# LED_RING_12V_00.net
KiCad netlist of a schematic drawn in Altium Designer
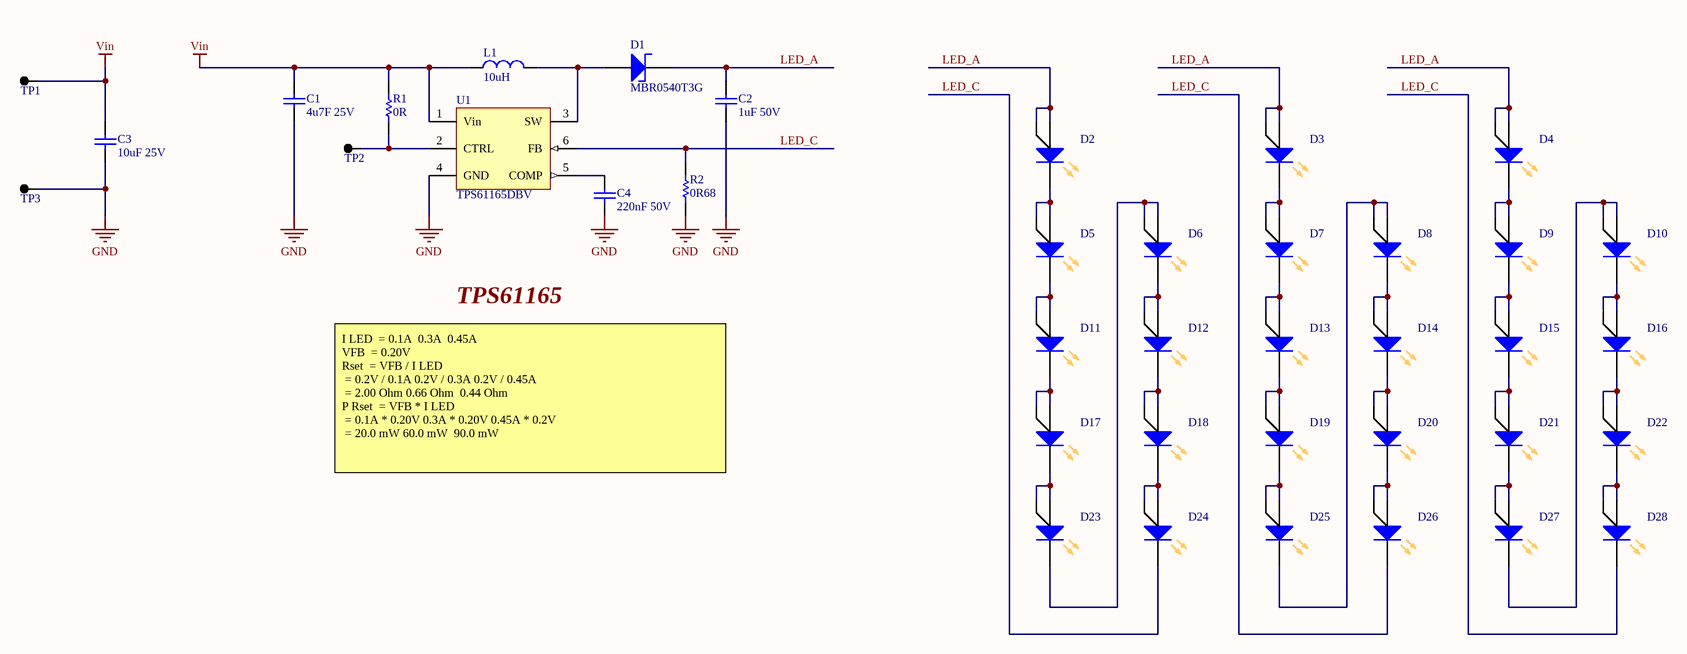
[diagram p0: LED_RING_12V_00.SchDoc]

(export (version "E")
  (design (tool "Eeschema 10.0.6"))
  (components
    (comp (ref "C1")
      (value "4u7F 25V")
      (footprint "C0805_N")
      (description "Capacitor Ceramic")
      (fields (field (name "Comment") "CAP_CERAMIC"))
      (libsource (lib "Phyx_Components") (part "CAP_CERAMIC"))
    )
    (comp (ref "C2")
      (value "1uF 50V")
      (footprint "C0805_N")
      (description "Capacitor Ceramic")
      (fields (field (name "Comment") "CAP_CERAMIC"))
      (libsource (lib "Phyx_Components") (part "CAP_CERAMIC"))
    )
    (comp (ref "C3")
      (value "10uF 25V")
      (footprint "C1206_N")
      (description "Capacitor Ceramic")
      (fields (field (name "Comment") "CAP_CERAMIC"))
      (libsource (lib "Phyx_Components") (part "CAP_CERAMIC"))
    )
    (comp (ref "C4")
      (value "220nF 50V")
      (footprint "C0603_N")
      (description "Capacitor Ceramic")
      (fields (field (name "Comment") "CAP_CERAMIC"))
      (libsource (lib "Phyx_Components") (part "CAP_CERAMIC"))
    )
    (comp (ref "D1")
      (value "MBR0540T3G")
      (footprint "ON_SOD-123FL")
      (description "=Description")
      (fields (field (name "Comment") "MBR0540T3G Schottky ULTRAFAST, 500MA, 40V"))
      (libsource (lib "Phyx_Components") (part "Schottky_21"))
    )
    (comp (ref "D2")
      (value "5630 5630AZLxx Lite ON LED")
      (footprint "LED_LM561A")
      (description "LED # LiteOn LTW-5630AZL27")
      (libsource (lib "Phyx_Components") (part "LED_5630AZLxx"))
    )
    (comp (ref "D3")
      (value "5630 5630AZLxx Lite ON LED")
      (footprint "LED_LM561A")
      (description "LED # LiteOn LTW-5630AZL27")
      (libsource (lib "Phyx_Components") (part "LED_5630AZLxx"))
    )
    (comp (ref "D4")
      (value "5630 5630AZLxx Lite ON LED")
      (footprint "LED_LM561A")
      (description "LED # LiteOn LTW-5630AZL27")
      (libsource (lib "Phyx_Components") (part "LED_5630AZLxx"))
    )
    (comp (ref "D5")
      (value "5630 5630AZLxx Lite ON LED")
      (footprint "LED_LM561A")
      (description "LED # LiteOn LTW-5630AZL27")
      (libsource (lib "Phyx_Components") (part "LED_5630AZLxx"))
    )
    (comp (ref "D6")
      (value "5630 5630AZLxx Lite ON LED")
      (footprint "LED_LM561A")
      (description "LED # LiteOn LTW-5630AZL27")
      (libsource (lib "Phyx_Components") (part "LED_5630AZLxx"))
    )
    (comp (ref "D7")
      (value "5630 5630AZLxx Lite ON LED")
      (footprint "LED_LM561A")
      (description "LED # LiteOn LTW-5630AZL27")
      (libsource (lib "Phyx_Components") (part "LED_5630AZLxx"))
    )
    (comp (ref "D8")
      (value "5630 5630AZLxx Lite ON LED")
      (footprint "LED_LM561A")
      (description "LED # LiteOn LTW-5630AZL27")
      (libsource (lib "Phyx_Components") (part "LED_5630AZLxx"))
    )
    (comp (ref "D9")
      (value "5630 5630AZLxx Lite ON LED")
      (footprint "LED_LM561A")
      (description "LED # LiteOn LTW-5630AZL27")
      (libsource (lib "Phyx_Components") (part "LED_5630AZLxx"))
    )
    (comp (ref "D10")
      (value "5630 5630AZLxx Lite ON LED")
      (footprint "LED_LM561A")
      (description "LED # LiteOn LTW-5630AZL27")
      (libsource (lib "Phyx_Components") (part "LED_5630AZLxx"))
    )
    (comp (ref "D11")
      (value "5630 5630AZLxx Lite ON LED")
      (footprint "LED_LM561A")
      (description "LED # LiteOn LTW-5630AZL27")
      (libsource (lib "Phyx_Components") (part "LED_5630AZLxx"))
    )
    (comp (ref "D12")
      (value "5630 5630AZLxx Lite ON LED")
      (footprint "LED_LM561A")
      (description "LED # LiteOn LTW-5630AZL27")
      (libsource (lib "Phyx_Components") (part "LED_5630AZLxx"))
    )
    (comp (ref "D13")
      (value "5630 5630AZLxx Lite ON LED")
      (footprint "LED_LM561A")
      (description "LED # LiteOn LTW-5630AZL27")
      (libsource (lib "Phyx_Components") (part "LED_5630AZLxx"))
    )
    (comp (ref "D14")
      (value "5630 5630AZLxx Lite ON LED")
      (footprint "LED_LM561A")
      (description "LED # LiteOn LTW-5630AZL27")
      (libsource (lib "Phyx_Components") (part "LED_5630AZLxx"))
    )
    (comp (ref "D15")
      (value "5630 5630AZLxx Lite ON LED")
      (footprint "LED_LM561A")
      (description "LED # LiteOn LTW-5630AZL27")
      (libsource (lib "Phyx_Components") (part "LED_5630AZLxx"))
    )
    (comp (ref "D16")
      (value "5630 5630AZLxx Lite ON LED")
      (footprint "LED_LM561A")
      (description "LED # LiteOn LTW-5630AZL27")
      (libsource (lib "Phyx_Components") (part "LED_5630AZLxx"))
    )
    (comp (ref "D17")
      (value "5630 5630AZLxx Lite ON LED")
      (footprint "LED_LM561A")
      (description "LED # LiteOn LTW-5630AZL27")
      (libsource (lib "Phyx_Components") (part "LED_5630AZLxx"))
    )
    (comp (ref "D18")
      (value "5630 5630AZLxx Lite ON LED")
      (footprint "LED_LM561A")
      (description "LED # LiteOn LTW-5630AZL27")
      (libsource (lib "Phyx_Components") (part "LED_5630AZLxx"))
    )
    (comp (ref "D19")
      (value "5630 5630AZLxx Lite ON LED")
      (footprint "LED_LM561A")
      (description "LED # LiteOn LTW-5630AZL27")
      (libsource (lib "Phyx_Components") (part "LED_5630AZLxx"))
    )
    (comp (ref "D20")
      (value "5630 5630AZLxx Lite ON LED")
      (footprint "LED_LM561A")
      (description "LED # LiteOn LTW-5630AZL27")
      (libsource (lib "Phyx_Components") (part "LED_5630AZLxx"))
    )
    (comp (ref "D21")
      (value "5630 5630AZLxx Lite ON LED")
      (footprint "LED_LM561A")
      (description "LED # LiteOn LTW-5630AZL27")
      (libsource (lib "Phyx_Components") (part "LED_5630AZLxx"))
    )
    (comp (ref "D22")
      (value "5630 5630AZLxx Lite ON LED")
      (footprint "LED_LM561A")
      (description "LED # LiteOn LTW-5630AZL27")
      (libsource (lib "Phyx_Components") (part "LED_5630AZLxx"))
    )
    (comp (ref "D23")
      (value "5630 5630AZLxx Lite ON LED")
      (footprint "LED_LM561A")
      (description "LED # LiteOn LTW-5630AZL27")
      (libsource (lib "Phyx_Components") (part "LED_5630AZLxx"))
    )
    (comp (ref "D24")
      (value "5630 5630AZLxx Lite ON LED")
      (footprint "LED_LM561A")
      (description "LED # LiteOn LTW-5630AZL27")
      (libsource (lib "Phyx_Components") (part "LED_5630AZLxx"))
    )
    (comp (ref "D25")
      (value "5630 5630AZLxx Lite ON LED")
      (footprint "LED_LM561A")
      (description "LED # LiteOn LTW-5630AZL27")
      (libsource (lib "Phyx_Components") (part "LED_5630AZLxx"))
    )
    (comp (ref "D26")
      (value "5630 5630AZLxx Lite ON LED")
      (footprint "LED_LM561A")
      (description "LED # LiteOn LTW-5630AZL27")
      (libsource (lib "Phyx_Components") (part "LED_5630AZLxx"))
    )
    (comp (ref "D27")
      (value "5630 5630AZLxx Lite ON LED")
      (footprint "LED_LM561A")
      (description "LED # LiteOn LTW-5630AZL27")
      (libsource (lib "Phyx_Components") (part "LED_5630AZLxx"))
    )
    (comp (ref "D28")
      (value "5630 5630AZLxx Lite ON LED")
      (footprint "LED_LM561A")
      (description "LED # LiteOn LTW-5630AZL27")
      (libsource (lib "Phyx_Components") (part "LED_5630AZLxx"))
    )
    (comp (ref "L1")
      (value "10uH")
      (footprint "LAIRD_TYS5020")
      (fields (field (name "Comment") "TYS5020100M-10"))
      (libsource (lib "Phyx_Components") (part "INDUCTOR"))
    )
    (comp (ref "R1")
      (value "0R")
      (footprint "R0603_N")
      (fields (field (name "Comment") "RESISTOR"))
      (libsource (lib "Phyx_Components") (part "RESISTOR"))
    )
    (comp (ref "R2")
      (value "0R68")
      (footprint "R1206")
      (fields (field (name "Comment") "RESISTOR"))
      (libsource (lib "Phyx_Components") (part "RESISTOR"))
    )
    (comp (ref "TP1")
      (value "TEST_PAD")
      (footprint "TP_2x3mm")
      (libsource (lib "Phyx_Components") (part "TEST_PAD"))
    )
    (comp (ref "TP2")
      (value "TEST_PAD")
      (footprint "TP_2x3mm")
      (libsource (lib "Phyx_Components") (part "TEST_PAD"))
    )
    (comp (ref "TP3")
      (value "TEST_PAD")
      (footprint "TP_2x3mm")
      (libsource (lib "Phyx_Components") (part "TEST_PAD"))
    )
    (comp (ref "U1")
      (value "TPS61165DBV")
      (footprint "TI_DBV_R-PDSO-G6")
      (description "=Description")
      (fields (field (name "Comment") "TPS61165 38-V Boost WLED Driver with PWM"))
      (libsource (lib "Phyx_Components") (part "TPS61165"))
    )
  )
  (nets
    (net (code "1") (name "/LED_A") (class "Default")
      (node (ref "C2") (pin "1") (pinfunction "1_1") (pintype "passive"))
      (node (ref "D1") (pin "1") (pinfunction "C_1") (pintype "passive"))
      (node (ref "D2") (pin "2") (pinfunction "K_2") (pintype "passive"))
      (node (ref "D2") (pin "3") (pinfunction "K_3") (pintype "passive"))
      (node (ref "D3") (pin "2") (pinfunction "K_2") (pintype "passive"))
      (node (ref "D3") (pin "3") (pinfunction "K_3") (pintype "passive"))
      (node (ref "D4") (pin "2") (pinfunction "K_2") (pintype "passive"))
      (node (ref "D4") (pin "3") (pinfunction "K_3") (pintype "passive"))
    )
    (net (code "2") (name "/LED_C") (class "Default")
      (node (ref "D24") (pin "1") (pinfunction "A_1") (pintype "passive"))
      (node (ref "D26") (pin "1") (pinfunction "A_1") (pintype "passive"))
      (node (ref "D28") (pin "1") (pinfunction "A_1") (pintype "passive"))
      (node (ref "R2") (pin "1") (pinfunction "1_1") (pintype "passive"))
      (node (ref "U1") (pin "6") (pinfunction "FB_6") (pintype "input"))
    )
    (net (code "3") (name "GND") (class "Default")
      (node (ref "C1") (pin "2") (pinfunction "2_2") (pintype "passive"))
      (node (ref "C2") (pin "2") (pinfunction "2_2") (pintype "passive"))
      (node (ref "C3") (pin "2") (pinfunction "2_2") (pintype "passive"))
      (node (ref "C4") (pin "2") (pinfunction "2_2") (pintype "passive"))
      (node (ref "R2") (pin "2") (pinfunction "2_2") (pintype "passive"))
      (node (ref "TP3") (pin "1") (pinfunction "1_1") (pintype "passive"))
      (node (ref "U1") (pin "4") (pinfunction "GND_4") (pintype "power_in"))
    )
    (net (code "4") (name "Net-(D1-A)") (class "Default")
      (node (ref "D1") (pin "2") (pinfunction "A_2") (pintype "passive"))
      (node (ref "L1") (pin "2") (pinfunction "2_2") (pintype "passive"))
      (node (ref "U1") (pin "3") (pinfunction "SW_3") (pintype "passive"))
    )
    (net (code "5") (name "Net-(D2-A)") (class "Default")
      (node (ref "D2") (pin "1") (pinfunction "A_1") (pintype "passive"))
      (node (ref "D5") (pin "2") (pinfunction "K_2") (pintype "passive"))
      (node (ref "D5") (pin "3") (pinfunction "K_3") (pintype "passive"))
    )
    (net (code "6") (name "Net-(D3-A)") (class "Default")
      (node (ref "D3") (pin "1") (pinfunction "A_1") (pintype "passive"))
      (node (ref "D7") (pin "2") (pinfunction "K_2") (pintype "passive"))
      (node (ref "D7") (pin "3") (pinfunction "K_3") (pintype "passive"))
    )
    (net (code "7") (name "Net-(D4-A)") (class "Default")
      (node (ref "D4") (pin "1") (pinfunction "A_1") (pintype "passive"))
      (node (ref "D9") (pin "2") (pinfunction "K_2") (pintype "passive"))
      (node (ref "D9") (pin "3") (pinfunction "K_3") (pintype "passive"))
    )
    (net (code "8") (name "Net-(D5-A)") (class "Default")
      (node (ref "D11") (pin "2") (pinfunction "K_2") (pintype "passive"))
      (node (ref "D11") (pin "3") (pinfunction "K_3") (pintype "passive"))
      (node (ref "D5") (pin "1") (pinfunction "A_1") (pintype "passive"))
    )
    (net (code "9") (name "Net-(D6-A)") (class "Default")
      (node (ref "D12") (pin "2") (pinfunction "K_2") (pintype "passive"))
      (node (ref "D12") (pin "3") (pinfunction "K_3") (pintype "passive"))
      (node (ref "D6") (pin "1") (pinfunction "A_1") (pintype "passive"))
    )
    (net (code "10") (name "Net-(D7-A)") (class "Default")
      (node (ref "D13") (pin "2") (pinfunction "K_2") (pintype "passive"))
      (node (ref "D13") (pin "3") (pinfunction "K_3") (pintype "passive"))
      (node (ref "D7") (pin "1") (pinfunction "A_1") (pintype "passive"))
    )
    (net (code "11") (name "Net-(D8-A)") (class "Default")
      (node (ref "D14") (pin "2") (pinfunction "K_2") (pintype "passive"))
      (node (ref "D14") (pin "3") (pinfunction "K_3") (pintype "passive"))
      (node (ref "D8") (pin "1") (pinfunction "A_1") (pintype "passive"))
    )
    (net (code "12") (name "Net-(D9-A)") (class "Default")
      (node (ref "D15") (pin "2") (pinfunction "K_2") (pintype "passive"))
      (node (ref "D15") (pin "3") (pinfunction "K_3") (pintype "passive"))
      (node (ref "D9") (pin "1") (pinfunction "A_1") (pintype "passive"))
    )
    (net (code "13") (name "Net-(D10-A)") (class "Default")
      (node (ref "D10") (pin "1") (pinfunction "A_1") (pintype "passive"))
      (node (ref "D16") (pin "2") (pinfunction "K_2") (pintype "passive"))
      (node (ref "D16") (pin "3") (pinfunction "K_3") (pintype "passive"))
    )
    (net (code "14") (name "Net-(D11-A)") (class "Default")
      (node (ref "D11") (pin "1") (pinfunction "A_1") (pintype "passive"))
      (node (ref "D17") (pin "2") (pinfunction "K_2") (pintype "passive"))
      (node (ref "D17") (pin "3") (pinfunction "K_3") (pintype "passive"))
    )
    (net (code "15") (name "Net-(D12-A)") (class "Default")
      (node (ref "D12") (pin "1") (pinfunction "A_1") (pintype "passive"))
      (node (ref "D18") (pin "2") (pinfunction "K_2") (pintype "passive"))
      (node (ref "D18") (pin "3") (pinfunction "K_3") (pintype "passive"))
    )
    (net (code "16") (name "Net-(D13-A)") (class "Default")
      (node (ref "D13") (pin "1") (pinfunction "A_1") (pintype "passive"))
      (node (ref "D19") (pin "2") (pinfunction "K_2") (pintype "passive"))
      (node (ref "D19") (pin "3") (pinfunction "K_3") (pintype "passive"))
    )
    (net (code "17") (name "Net-(D14-A)") (class "Default")
      (node (ref "D14") (pin "1") (pinfunction "A_1") (pintype "passive"))
      (node (ref "D20") (pin "2") (pinfunction "K_2") (pintype "passive"))
      (node (ref "D20") (pin "3") (pinfunction "K_3") (pintype "passive"))
    )
    (net (code "18") (name "Net-(D15-A)") (class "Default")
      (node (ref "D15") (pin "1") (pinfunction "A_1") (pintype "passive"))
      (node (ref "D21") (pin "2") (pinfunction "K_2") (pintype "passive"))
      (node (ref "D21") (pin "3") (pinfunction "K_3") (pintype "passive"))
    )
    (net (code "19") (name "Net-(D16-A)") (class "Default")
      (node (ref "D16") (pin "1") (pinfunction "A_1") (pintype "passive"))
      (node (ref "D22") (pin "2") (pinfunction "K_2") (pintype "passive"))
      (node (ref "D22") (pin "3") (pinfunction "K_3") (pintype "passive"))
    )
    (net (code "20") (name "Net-(D17-A)") (class "Default")
      (node (ref "D17") (pin "1") (pinfunction "A_1") (pintype "passive"))
      (node (ref "D23") (pin "2") (pinfunction "K_2") (pintype "passive"))
      (node (ref "D23") (pin "3") (pinfunction "K_3") (pintype "passive"))
    )
    (net (code "21") (name "Net-(D18-A)") (class "Default")
      (node (ref "D18") (pin "1") (pinfunction "A_1") (pintype "passive"))
      (node (ref "D24") (pin "2") (pinfunction "K_2") (pintype "passive"))
      (node (ref "D24") (pin "3") (pinfunction "K_3") (pintype "passive"))
    )
    (net (code "22") (name "Net-(D19-A)") (class "Default")
      (node (ref "D19") (pin "1") (pinfunction "A_1") (pintype "passive"))
      (node (ref "D25") (pin "2") (pinfunction "K_2") (pintype "passive"))
      (node (ref "D25") (pin "3") (pinfunction "K_3") (pintype "passive"))
    )
    (net (code "23") (name "Net-(D20-A)") (class "Default")
      (node (ref "D20") (pin "1") (pinfunction "A_1") (pintype "passive"))
      (node (ref "D26") (pin "2") (pinfunction "K_2") (pintype "passive"))
      (node (ref "D26") (pin "3") (pinfunction "K_3") (pintype "passive"))
    )
    (net (code "24") (name "Net-(D21-A)") (class "Default")
      (node (ref "D21") (pin "1") (pinfunction "A_1") (pintype "passive"))
      (node (ref "D27") (pin "2") (pinfunction "K_2") (pintype "passive"))
      (node (ref "D27") (pin "3") (pinfunction "K_3") (pintype "passive"))
    )
    (net (code "25") (name "Net-(D22-A)") (class "Default")
      (node (ref "D22") (pin "1") (pinfunction "A_1") (pintype "passive"))
      (node (ref "D28") (pin "2") (pinfunction "K_2") (pintype "passive"))
      (node (ref "D28") (pin "3") (pinfunction "K_3") (pintype "passive"))
    )
    (net (code "26") (name "Net-(D23-A)") (class "Default")
      (node (ref "D23") (pin "1") (pinfunction "A_1") (pintype "passive"))
      (node (ref "D6") (pin "2") (pinfunction "K_2") (pintype "passive"))
      (node (ref "D6") (pin "3") (pinfunction "K_3") (pintype "passive"))
    )
    (net (code "27") (name "Net-(D25-A)") (class "Default")
      (node (ref "D25") (pin "1") (pinfunction "A_1") (pintype "passive"))
      (node (ref "D8") (pin "2") (pinfunction "K_2") (pintype "passive"))
      (node (ref "D8") (pin "3") (pinfunction "K_3") (pintype "passive"))
    )
    (net (code "28") (name "Net-(D27-A)") (class "Default")
      (node (ref "D10") (pin "2") (pinfunction "K_2") (pintype "passive"))
      (node (ref "D10") (pin "3") (pinfunction "K_3") (pintype "passive"))
      (node (ref "D27") (pin "1") (pinfunction "A_1") (pintype "passive"))
    )
    (net (code "29") (name "Net-(U1-COMP)") (class "Default")
      (node (ref "C4") (pin "1") (pinfunction "1_1") (pintype "passive"))
      (node (ref "U1") (pin "5") (pinfunction "COMP_5") (pintype "output"))
    )
    (net (code "30") (name "Net-(U1-CTRL)") (class "Default")
      (node (ref "R1") (pin "2") (pinfunction "2_2") (pintype "passive"))
      (node (ref "TP2") (pin "1") (pinfunction "1_1") (pintype "passive"))
      (node (ref "U1") (pin "2") (pinfunction "CTRL_2") (pintype "passive"))
    )
    (net (code "31") (name "Vin") (class "Default")
      (node (ref "C1") (pin "1") (pinfunction "1_1") (pintype "passive"))
      (node (ref "C3") (pin "1") (pinfunction "1_1") (pintype "passive"))
      (node (ref "L1") (pin "1") (pinfunction "1_1") (pintype "passive"))
      (node (ref "R1") (pin "1") (pinfunction "1_1") (pintype "passive"))
      (node (ref "TP1") (pin "1") (pinfunction "1_1") (pintype "passive"))
      (node (ref "U1") (pin "1") (pinfunction "Vin_1") (pintype "power_in"))
    )
  )
)
